# RoomIndicator_Inside.net
KiCad netlist of a schematic drawn in EAGLE
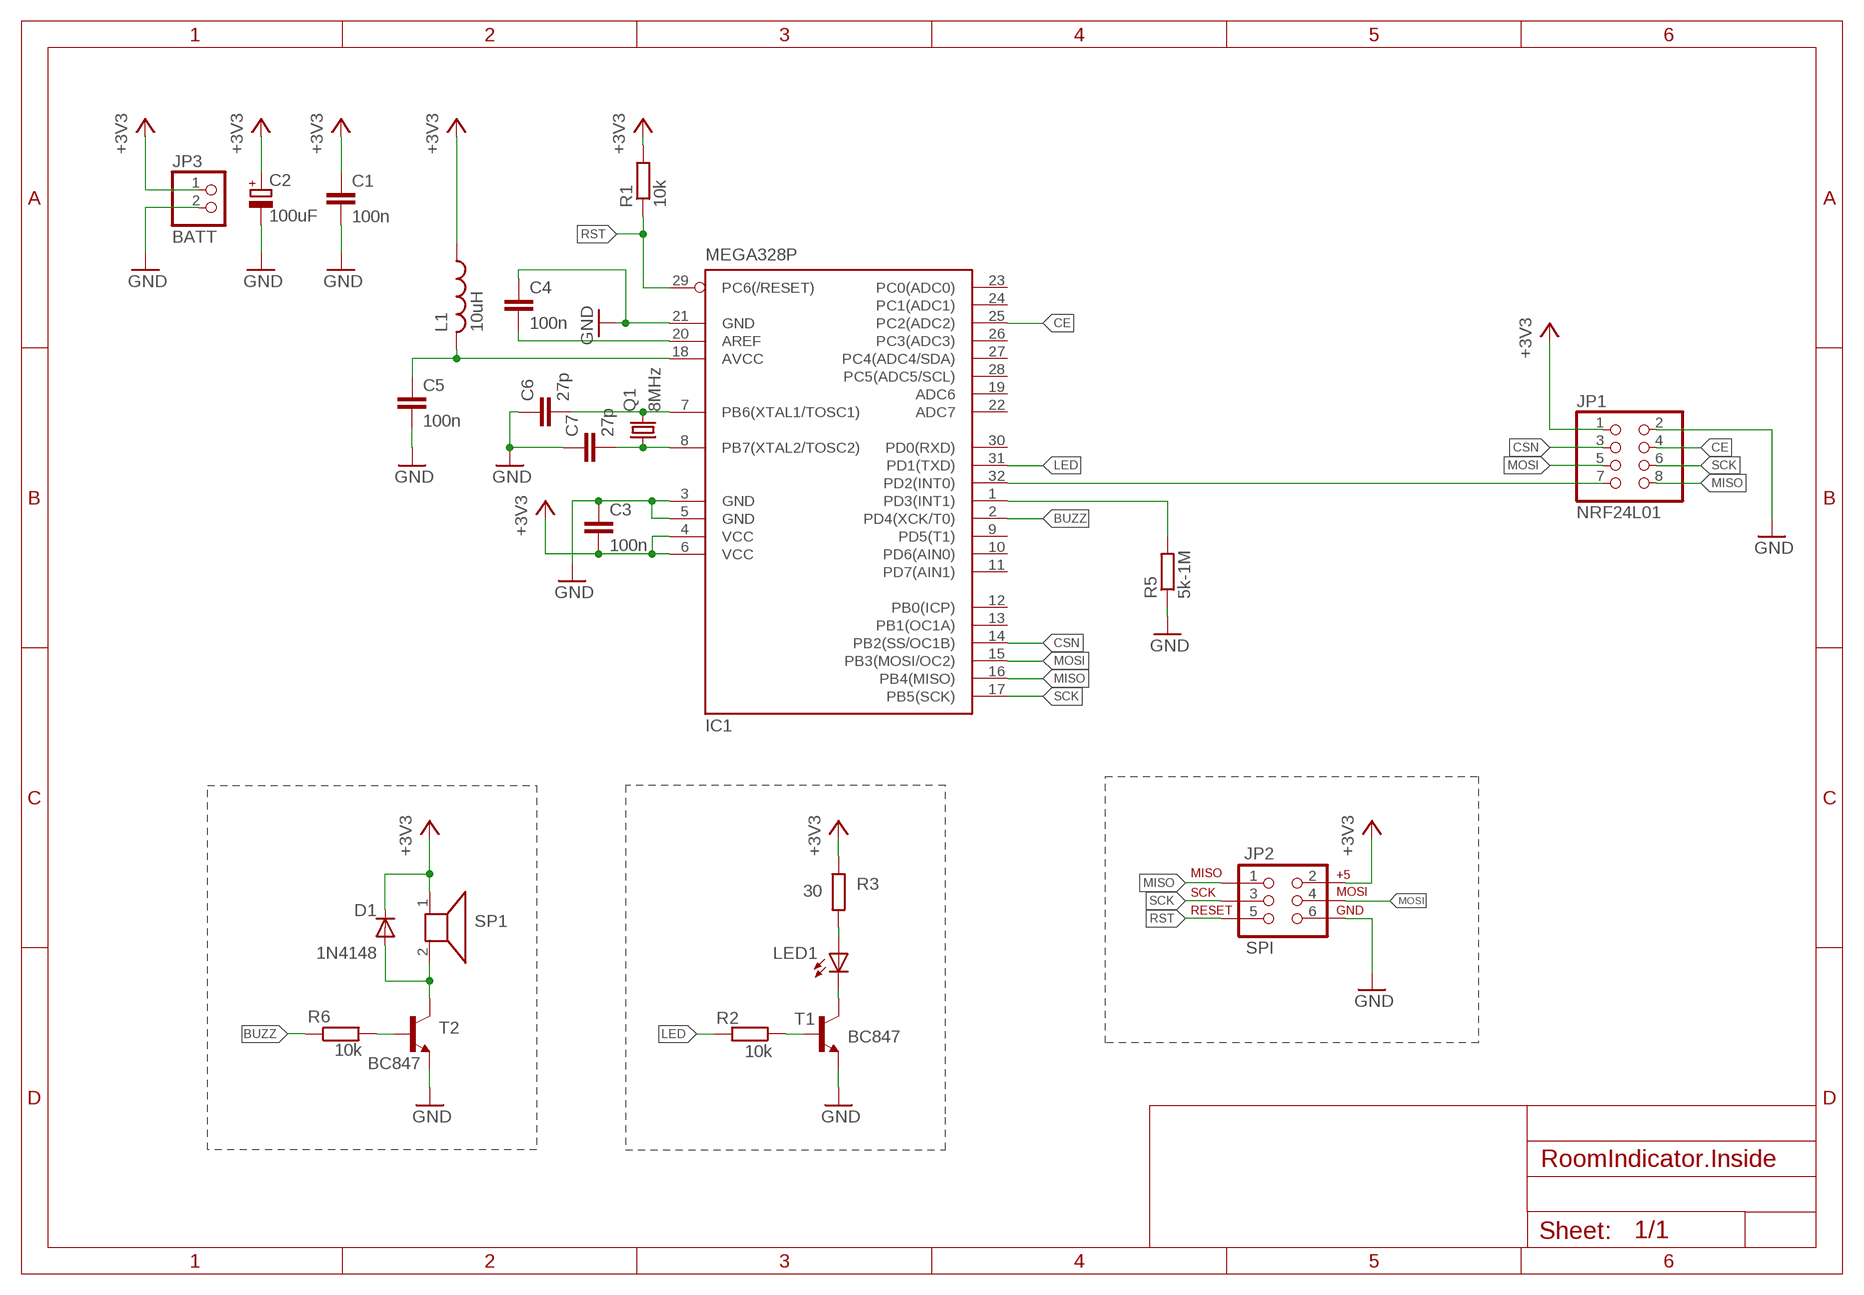
[diagram p0: schematic, sheet 1]

(export (version "E")
  (design (tool "Eeschema 10.0.6"))
  (components
    (comp (ref "C1")
      (value "100n")
      (footprint "eagle-import:C025-025X050")
      (libsource (lib "eagle-import") (part "C-EU025-025X050"))
    )
    (comp (ref "C2")
      (value "100uF")
      (footprint "eagle-import:E2,5-5")
      (libsource (lib "eagle-import") (part "CPOL-EUE2.5-5"))
    )
    (comp (ref "C3")
      (value "100n")
      (footprint "eagle-import:C0805K")
      (libsource (lib "eagle-import") (part "C-EUC0805K"))
    )
    (comp (ref "C4")
      (value "100n")
      (footprint "eagle-import:C0805K")
      (libsource (lib "eagle-import") (part "C-EUC0805K"))
    )
    (comp (ref "C5")
      (value "100n")
      (footprint "eagle-import:C0805K")
      (libsource (lib "eagle-import") (part "C-EUC0805K"))
    )
    (comp (ref "C6")
      (value "27p")
      (footprint "eagle-import:C0805K")
      (libsource (lib "eagle-import") (part "C-EUC0805K"))
    )
    (comp (ref "C7")
      (value "27p")
      (footprint "eagle-import:C0805K")
      (libsource (lib "eagle-import") (part "C-EUC0805K"))
    )
    (comp (ref "D1")
      (value "1N4148")
      (footprint "eagle-import:DO35-7")
      (libsource (lib "eagle-import") (part "1N4148DO35-7"))
    )
    (comp (ref "IC1")
      (value "MEGA328P")
      (footprint "eagle-import:TQFP32-08")
      (fields (field (name "MPN") "ATMEGA8-16AU"))
      (libsource (lib "eagle-import") (part "MEGA8-AI"))
    )
    (comp (ref "JP1")
      (value "NRF24L01")
      (footprint "eagle-import:2X04")
      (libsource (lib "eagle-import") (part "PINHD-2X4"))
    )
    (comp (ref "JP2")
      (value "SPI")
      (footprint "eagle-import:2X3")
      (libsource (lib "eagle-import") (part "AVR_SPI_PRG_6PTH"))
    )
    (comp (ref "JP3")
      (value "BATT")
      (footprint "eagle-import:1X02")
      (libsource (lib "eagle-import") (part "PINHD-1X2"))
    )
    (comp (ref "L1")
      (value "10uH")
      (footprint "eagle-import:0204_7")
      (libsource (lib "eagle-import") (part "L-US0204/7"))
    )
    (comp (ref "LED1")
      (value "GREEN")
      (footprint "eagle-import:LED5MM")
      (libsource (lib "eagle-import") (part "LED5MM"))
    )
    (comp (ref "Q1")
      (value "8MHz")
      (footprint "eagle-import:HC49_S")
      (libsource (lib "eagle-import") (part "CRYSTALHC49S"))
    )
    (comp (ref "R1")
      (value "10k")
      (footprint "eagle-import:R0805")
      (libsource (lib "eagle-import") (part "R-EU_R0805"))
    )
    (comp (ref "R2")
      (value "10k")
      (footprint "eagle-import:R0805")
      (libsource (lib "eagle-import") (part "R-EU_R0805"))
    )
    (comp (ref "R3")
      (value "30")
      (footprint "eagle-import:0204_5")
      (libsource (lib "eagle-import") (part "R-EU_0204/5"))
    )
    (comp (ref "R5")
      (value "5k-1M")
      (footprint "eagle-import:0204_5")
      (libsource (lib "eagle-import") (part "R-EU_0204/5"))
    )
    (comp (ref "R6")
      (value "10k")
      (footprint "eagle-import:R0805")
      (libsource (lib "eagle-import") (part "R-EU_R0805"))
    )
    (comp (ref "SP1")
      (value "AL60P")
      (footprint "eagle-import:AL60P")
      (libsource (lib "eagle-import") (part "AL60P"))
    )
    (comp (ref "T1")
      (value "BC847")
      (footprint "eagle-import:SOT23")
      (libsource (lib "eagle-import") (part "BC847"))
    )
    (comp (ref "T2")
      (value "BC847")
      (footprint "eagle-import:SOT23")
      (libsource (lib "eagle-import") (part "BC847"))
    )
  )
  (nets
    (net (code "1") (name "+3V3") (class "Default")
      (node (ref "C1") (pin "1") (pinfunction "1_1") (pintype "passive"))
      (node (ref "C2") (pin "+") (pinfunction "+_+") (pintype "passive"))
      (node (ref "C3") (pin "2") (pinfunction "2_2") (pintype "passive"))
      (node (ref "D1") (pin "C") (pinfunction "C_C") (pintype "passive"))
      (node (ref "IC1") (pin "4") (pinfunction "VCC_4") (pintype "power_in"))
      (node (ref "IC1") (pin "6") (pinfunction "VCC_6") (pintype "power_in"))
      (node (ref "JP1") (pin "1") (pinfunction "1_1") (pintype "passive"))
      (node (ref "JP2") (pin "2") (pinfunction "2_2") (pintype "passive"))
      (node (ref "JP3") (pin "1") (pinfunction "1_1") (pintype "passive"))
      (node (ref "L1") (pin "1") (pinfunction "1_1") (pintype "passive"))
      (node (ref "R1") (pin "2") (pinfunction "2_2") (pintype "passive"))
      (node (ref "R3") (pin "1") (pinfunction "1_1") (pintype "passive"))
      (node (ref "SP1") (pin "1") (pinfunction "1_1") (pintype "passive"))
    )
    (net (code "2") (name "BUZZ") (class "Default")
      (node (ref "IC1") (pin "2") (pinfunction "PD4(XCK/T0)_2") (pintype "bidirectional"))
      (node (ref "R6") (pin "1") (pinfunction "1_1") (pintype "passive"))
    )
    (net (code "3") (name "CE") (class "Default")
      (node (ref "IC1") (pin "25") (pinfunction "PC2(ADC2)_25") (pintype "bidirectional"))
      (node (ref "JP1") (pin "4") (pinfunction "4_4") (pintype "passive"))
    )
    (net (code "4") (name "CSN") (class "Default")
      (node (ref "IC1") (pin "14") (pinfunction "PB2(SS/OC1B)_14") (pintype "bidirectional"))
      (node (ref "JP1") (pin "3") (pinfunction "3_3") (pintype "passive"))
    )
    (net (code "5") (name "GND") (class "Default")
      (node (ref "C1") (pin "2") (pinfunction "2_2") (pintype "passive"))
      (node (ref "C2") (pin "-") (pinfunction "-_-") (pintype "passive"))
      (node (ref "C3") (pin "1") (pinfunction "1_1") (pintype "passive"))
      (node (ref "C4") (pin "1") (pinfunction "1_1") (pintype "passive"))
      (node (ref "C5") (pin "2") (pinfunction "2_2") (pintype "passive"))
      (node (ref "C6") (pin "1") (pinfunction "1_1") (pintype "passive"))
      (node (ref "C7") (pin "1") (pinfunction "1_1") (pintype "passive"))
      (node (ref "IC1") (pin "21") (pinfunction "GND_21") (pintype "power_in"))
      (node (ref "IC1") (pin "3") (pinfunction "GND_3") (pintype "power_in"))
      (node (ref "IC1") (pin "5") (pinfunction "GND_5") (pintype "power_in"))
      (node (ref "JP1") (pin "2") (pinfunction "2_2") (pintype "passive"))
      (node (ref "JP2") (pin "6") (pinfunction "6_6") (pintype "passive"))
      (node (ref "JP3") (pin "2") (pinfunction "2_2") (pintype "passive"))
      (node (ref "R5") (pin "1") (pinfunction "1_1") (pintype "passive"))
      (node (ref "T1") (pin "2") (pinfunction "E_2") (pintype "passive"))
      (node (ref "T2") (pin "2") (pinfunction "E_2") (pintype "passive"))
    )
    (net (code "6") (name "LED") (class "Default")
      (node (ref "IC1") (pin "31") (pinfunction "PD1(TXD)_31") (pintype "bidirectional"))
      (node (ref "R2") (pin "2") (pinfunction "2_2") (pintype "passive"))
    )
    (net (code "7") (name "MISO") (class "Default")
      (node (ref "IC1") (pin "16") (pinfunction "PB4(MISO)_16") (pintype "bidirectional"))
      (node (ref "JP1") (pin "8") (pinfunction "8_8") (pintype "passive"))
      (node (ref "JP2") (pin "1") (pinfunction "1_1") (pintype "passive"))
    )
    (net (code "8") (name "MOSI") (class "Default")
      (node (ref "IC1") (pin "15") (pinfunction "PB3(MOSI/OC2)_15") (pintype "bidirectional"))
      (node (ref "JP1") (pin "5") (pinfunction "5_5") (pintype "passive"))
      (node (ref "JP2") (pin "4") (pinfunction "4_4") (pintype "passive"))
    )
    (net (code "9") (name "Net-(IC1-AREF)") (class "Default")
      (node (ref "C4") (pin "2") (pinfunction "2_2") (pintype "passive"))
      (node (ref "IC1") (pin "20") (pinfunction "AREF_20") (pintype "passive"))
    )
    (net (code "10") (name "Net-(IC1-AVCC)") (class "Default")
      (node (ref "C5") (pin "1") (pinfunction "1_1") (pintype "passive"))
      (node (ref "IC1") (pin "18") (pinfunction "AVCC_18") (pintype "power_in"))
      (node (ref "L1") (pin "2") (pinfunction "2_2") (pintype "passive"))
    )
    (net (code "11") (name "Net-(IC1-PB6(XTAL1{slash}TOSC1))") (class "Default")
      (node (ref "C6") (pin "2") (pinfunction "2_2") (pintype "passive"))
      (node (ref "IC1") (pin "7") (pinfunction "PB6(XTAL1/TOSC1)_7") (pintype "bidirectional"))
      (node (ref "Q1") (pin "2") (pinfunction "2_2") (pintype "passive"))
    )
    (net (code "12") (name "Net-(IC1-PB7(XTAL2{slash}TOSC2))") (class "Default")
      (node (ref "C7") (pin "2") (pinfunction "2_2") (pintype "passive"))
      (node (ref "IC1") (pin "8") (pinfunction "PB7(XTAL2/TOSC2)_8") (pintype "bidirectional"))
      (node (ref "Q1") (pin "1") (pinfunction "1_1") (pintype "passive"))
    )
    (net (code "13") (name "Net-(IC1-PD2(INT0))") (class "Default")
      (node (ref "IC1") (pin "32") (pinfunction "PD2(INT0)_32") (pintype "bidirectional"))
      (node (ref "JP1") (pin "7") (pinfunction "7_7") (pintype "passive"))
    )
    (net (code "14") (name "Net-(IC1-PD3(INT1))") (class "Default")
      (node (ref "IC1") (pin "1") (pinfunction "PD3(INT1)_1") (pintype "bidirectional"))
      (node (ref "R5") (pin "2") (pinfunction "2_2") (pintype "passive"))
    )
    (net (code "15") (name "Net-(LED1-C)") (class "Default")
      (node (ref "LED1") (pin "K") (pinfunction "C_K") (pintype "passive"))
      (node (ref "T1") (pin "3") (pinfunction "C_3") (pintype "passive"))
    )
    (net (code "16") (name "Net-(LED1-PadA)") (class "Default")
      (node (ref "LED1") (pin "A") (pinfunction "A_A") (pintype "passive"))
      (node (ref "R3") (pin "2") (pinfunction "2_2") (pintype "passive"))
    )
    (net (code "17") (name "Net-(T1-B)") (class "Default")
      (node (ref "R2") (pin "1") (pinfunction "1_1") (pintype "passive"))
      (node (ref "T1") (pin "1") (pinfunction "B_1") (pintype "passive"))
    )
    (net (code "18") (name "Net-(T2-B)") (class "Default")
      (node (ref "R6") (pin "2") (pinfunction "2_2") (pintype "passive"))
      (node (ref "T2") (pin "1") (pinfunction "B_1") (pintype "passive"))
    )
    (net (code "19") (name "Net-(T2-C)") (class "Default")
      (node (ref "D1") (pin "A") (pinfunction "A_A") (pintype "passive"))
      (node (ref "SP1") (pin "2") (pinfunction "2_2") (pintype "passive"))
      (node (ref "T2") (pin "3") (pinfunction "C_3") (pintype "passive"))
    )
    (net (code "20") (name "RST") (class "Default")
      (node (ref "IC1") (pin "29") (pinfunction "PC6(/RESET)_29") (pintype "bidirectional"))
      (node (ref "JP2") (pin "5") (pinfunction "5_5") (pintype "passive"))
      (node (ref "R1") (pin "1") (pinfunction "1_1") (pintype "passive"))
    )
    (net (code "21") (name "SCK") (class "Default")
      (node (ref "IC1") (pin "17") (pinfunction "PB5(SCK)_17") (pintype "bidirectional"))
      (node (ref "JP1") (pin "6") (pinfunction "6_6") (pintype "passive"))
      (node (ref "JP2") (pin "3") (pinfunction "3_3") (pintype "passive"))
    )
    (net (code "22") (name "unconnected-(IC1-ADC6-Pad19)") (class "Default")
      (node (ref "IC1") (pin "19") (pinfunction "ADC6_19") (pintype "bidirectional"))
    )
    (net (code "23") (name "unconnected-(IC1-ADC7-Pad22)") (class "Default")
      (node (ref "IC1") (pin "22") (pinfunction "ADC7_22") (pintype "bidirectional"))
    )
    (net (code "24") (name "unconnected-(IC1-PB0(ICP)-Pad12)") (class "Default")
      (node (ref "IC1") (pin "12") (pinfunction "PB0(ICP)_12") (pintype "bidirectional"))
    )
    (net (code "25") (name "unconnected-(IC1-PB1(OC1A)-Pad13)") (class "Default")
      (node (ref "IC1") (pin "13") (pinfunction "PB1(OC1A)_13") (pintype "bidirectional"))
    )
    (net (code "26") (name "unconnected-(IC1-PC0(ADC0)-Pad23)") (class "Default")
      (node (ref "IC1") (pin "23") (pinfunction "PC0(ADC0)_23") (pintype "bidirectional"))
    )
    (net (code "27") (name "unconnected-(IC1-PC1(ADC1)-Pad24)") (class "Default")
      (node (ref "IC1") (pin "24") (pinfunction "PC1(ADC1)_24") (pintype "bidirectional"))
    )
    (net (code "28") (name "unconnected-(IC1-PC3(ADC3)-Pad26)") (class "Default")
      (node (ref "IC1") (pin "26") (pinfunction "PC3(ADC3)_26") (pintype "bidirectional"))
    )
    (net (code "29") (name "unconnected-(IC1-PC4(ADC4{slash}SDA)-Pad27)") (class "Default")
      (node (ref "IC1") (pin "27") (pinfunction "PC4(ADC4/SDA)_27") (pintype "bidirectional"))
    )
    (net (code "30") (name "unconnected-(IC1-PC5(ADC5{slash}SCL)-Pad28)") (class "Default")
      (node (ref "IC1") (pin "28") (pinfunction "PC5(ADC5/SCL)_28") (pintype "bidirectional"))
    )
    (net (code "31") (name "unconnected-(IC1-PD0(RXD)-Pad30)") (class "Default")
      (node (ref "IC1") (pin "30") (pinfunction "PD0(RXD)_30") (pintype "bidirectional"))
    )
    (net (code "32") (name "unconnected-(IC1-PD5(T1)-Pad9)") (class "Default")
      (node (ref "IC1") (pin "9") (pinfunction "PD5(T1)_9") (pintype "bidirectional"))
    )
    (net (code "33") (name "unconnected-(IC1-PD6(AIN0)-Pad10)") (class "Default")
      (node (ref "IC1") (pin "10") (pinfunction "PD6(AIN0)_10") (pintype "bidirectional"))
    )
    (net (code "34") (name "unconnected-(IC1-PD7(AIN1)-Pad11)") (class "Default")
      (node (ref "IC1") (pin "11") (pinfunction "PD7(AIN1)_11") (pintype "bidirectional"))
    )
  )
)
